# alpha_board.net
KiCad netlist of a schematic drawn in EAGLE
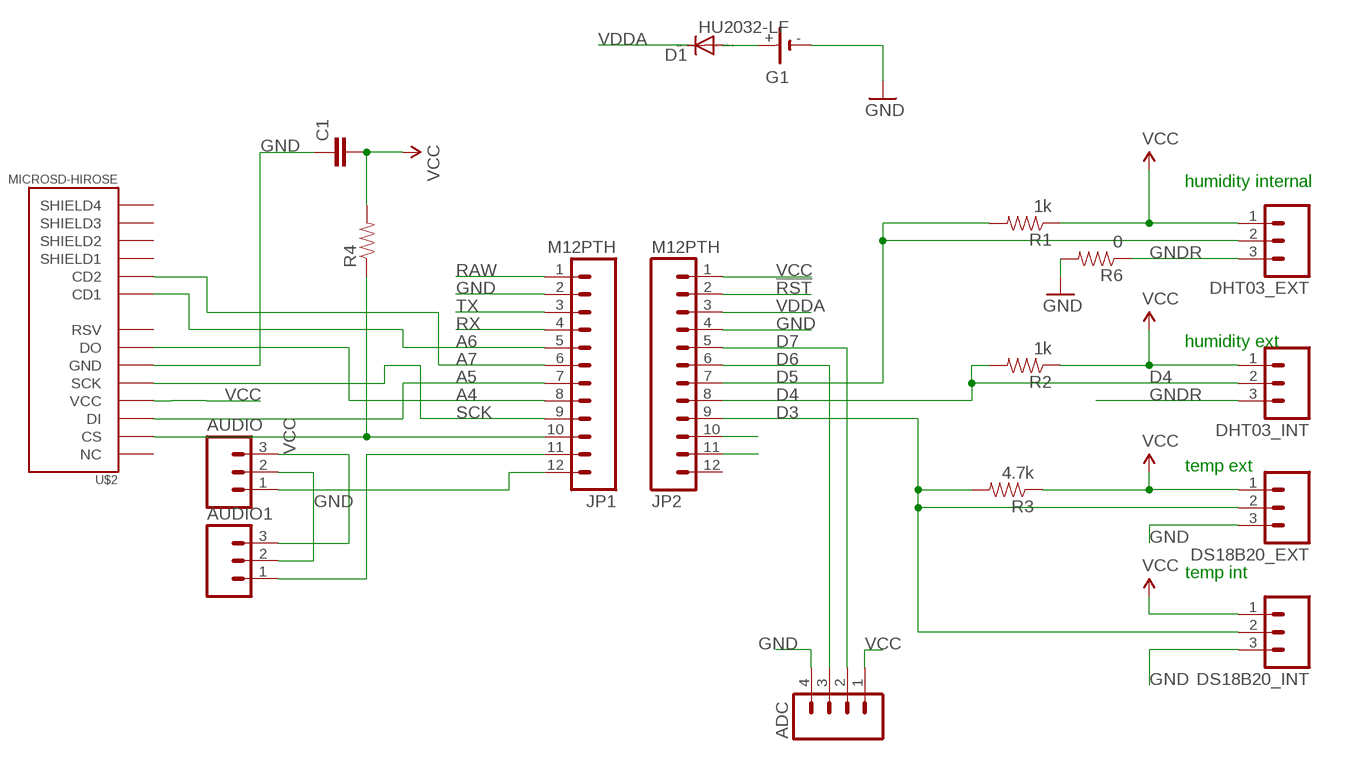
[diagram p0: schematic, sheet 1]

(export (version "E")
  (design (tool "Eeschema 10.0.6"))
  (components
    (comp (ref "ADC")
      (value "M04LOCK_LONGPADS")
      (footprint "eagle-import:1X04_LOCK_LONGPADS")
      (libsource (lib "eagle-import") (part "M04LOCK_LONGPADS"))
    )
    (comp (ref "AUDIO")
      (value "M03LOCK")
      (footprint "eagle-import:1X03_LOCK")
      (libsource (lib "eagle-import") (part "M03LOCK"))
    )
    (comp (ref "AUDIO1")
      (value "M03LOCK")
      (footprint "eagle-import:1X03_LOCK")
      (libsource (lib "eagle-import") (part "M03LOCK"))
    )
    (comp (ref "C1")
      (value "CAP1206")
      (footprint "eagle-import:1206")
      (libsource (lib "eagle-import") (part "CAP1206"))
    )
    (comp (ref "D1")
      (value "DIODE-SOD323-W")
      (footprint "eagle-import:SOD323-W")
      (libsource (lib "eagle-import") (part "DIODE-SOD323-W"))
    )
    (comp (ref "DHT03_EXT")
      (value "M03LOCK")
      (footprint "eagle-import:1X03_LOCK")
      (libsource (lib "eagle-import") (part "M03LOCK"))
    )
    (comp (ref "DHT03_INT")
      (value "M03LOCK")
      (footprint "eagle-import:1X03_LOCK")
      (libsource (lib "eagle-import") (part "M03LOCK"))
    )
    (comp (ref "DS18B20_EXT")
      (value "M03LOCK")
      (footprint "eagle-import:1X03_LOCK")
      (libsource (lib "eagle-import") (part "M03LOCK"))
    )
    (comp (ref "DS18B20_INT")
      (value "M03LOCK")
      (footprint "eagle-import:1X03_LOCK")
      (libsource (lib "eagle-import") (part "M03LOCK"))
    )
    (comp (ref "G1")
      (value "HU2032-LF")
      (footprint "eagle-import:HU2032-LF")
      (libsource (lib "eagle-import") (part "HU2032-LF"))
    )
    (comp (ref "JP1")
      (value "M12PTH")
      (footprint "eagle-import:1X12-SMALL-PADS")
      (libsource (lib "eagle-import") (part "M12PTH"))
    )
    (comp (ref "JP2")
      (value "M12PTH")
      (footprint "eagle-import:1X12-SMALL-PADS")
      (libsource (lib "eagle-import") (part "M12PTH"))
    )
    (comp (ref "R1")
      (value "1k")
      (footprint "eagle-import:1206")
      (libsource (lib "eagle-import") (part "RESISTOR1206"))
    )
    (comp (ref "R2")
      (value "1k")
      (footprint "eagle-import:1206")
      (libsource (lib "eagle-import") (part "RESISTOR1206"))
    )
    (comp (ref "R3")
      (value "4.7k")
      (footprint "eagle-import:1206")
      (libsource (lib "eagle-import") (part "RESISTOR1206"))
    )
    (comp (ref "R4")
      (value "RESISTOR1206")
      (footprint "eagle-import:1206")
      (libsource (lib "eagle-import") (part "RESISTOR1206"))
    )
    (comp (ref "R6")
      (value "0")
      (footprint "eagle-import:1206")
      (libsource (lib "eagle-import") (part "RESISTOR1206"))
    )
    (comp (ref "U$2")
      (value "MICROSD-HIROSE")
      (footprint "eagle-import:MICROSD_HOLDER-HIROSE-DM3AT")
      (libsource (lib "eagle-import") (part "MICROSD-HIROSE"))
    )
  )
  (nets
    (net (code "1") (name "/A4") (class "Default")
      (node (ref "JP1") (pin "8") (pinfunction "8_8") (pintype "passive"))
      (node (ref "U$2") (pin "DAT0") (pinfunction "DO_DAT0") (pintype "bidirectional"))
    )
    (net (code "2") (name "/A5") (class "Default")
      (node (ref "JP1") (pin "7") (pinfunction "7_7") (pintype "passive"))
      (node (ref "U$2") (pin "CMD") (pinfunction "DI_CMD") (pintype "bidirectional"))
    )
    (net (code "3") (name "/A6") (class "Default")
      (node (ref "JP1") (pin "5") (pinfunction "5_5") (pintype "passive"))
      (node (ref "U$2") (pin "CD1") (pinfunction "CD1_CD1") (pintype "bidirectional"))
    )
    (net (code "4") (name "/A7") (class "Default")
      (node (ref "JP1") (pin "6") (pinfunction "6_6") (pintype "passive"))
      (node (ref "U$2") (pin "CD2") (pinfunction "CD2_CD2") (pintype "bidirectional"))
    )
    (net (code "5") (name "/D3") (class "Default")
      (node (ref "DS18B20_EXT") (pin "2") (pinfunction "2_2") (pintype "passive"))
      (node (ref "DS18B20_INT") (pin "2") (pinfunction "2_2") (pintype "passive"))
      (node (ref "JP2") (pin "9") (pinfunction "9_9") (pintype "passive"))
      (node (ref "R3") (pin "2") (pinfunction "2_2") (pintype "passive"))
    )
    (net (code "6") (name "/D4") (class "Default")
      (node (ref "DHT03_INT") (pin "2") (pinfunction "2_2") (pintype "passive"))
      (node (ref "JP2") (pin "8") (pinfunction "8_8") (pintype "passive"))
      (node (ref "R2") (pin "2") (pinfunction "2_2") (pintype "passive"))
    )
    (net (code "7") (name "/D5") (class "Default")
      (node (ref "DHT03_EXT") (pin "2") (pinfunction "2_2") (pintype "passive"))
      (node (ref "JP2") (pin "7") (pinfunction "7_7") (pintype "passive"))
      (node (ref "R1") (pin "2") (pinfunction "2_2") (pintype "passive"))
    )
    (net (code "8") (name "/D6") (class "Default")
      (node (ref "ADC") (pin "3") (pinfunction "3_3") (pintype "passive"))
      (node (ref "JP2") (pin "6") (pinfunction "6_6") (pintype "passive"))
    )
    (net (code "9") (name "/D7") (class "Default")
      (node (ref "ADC") (pin "2") (pinfunction "2_2") (pintype "passive"))
      (node (ref "JP2") (pin "5") (pinfunction "5_5") (pintype "passive"))
    )
    (net (code "10") (name "/GNDR") (class "Default")
      (node (ref "DHT03_EXT") (pin "3") (pinfunction "3_3") (pintype "passive"))
      (node (ref "DHT03_INT") (pin "3") (pinfunction "3_3") (pintype "passive"))
      (node (ref "R6") (pin "1") (pinfunction "1_1") (pintype "passive"))
    )
    (net (code "11") (name "/RAW") (class "Default")
      (node (ref "JP1") (pin "1") (pinfunction "1_1") (pintype "passive"))
    )
    (net (code "12") (name "/RX") (class "Default")
      (node (ref "JP1") (pin "4") (pinfunction "4_4") (pintype "passive"))
    )
    (net (code "13") (name "/SCK") (class "Default")
      (node (ref "JP1") (pin "9") (pinfunction "9_9") (pintype "passive"))
      (node (ref "U$2") (pin "CLK") (pinfunction "SCK_CLK") (pintype "bidirectional"))
    )
    (net (code "14") (name "/TX") (class "Default")
      (node (ref "JP1") (pin "3") (pinfunction "3_3") (pintype "passive"))
    )
    (net (code "15") (name "/VDDA") (class "Default")
      (node (ref "D1") (pin "C") (pinfunction "C_C") (pintype "passive"))
      (node (ref "JP2") (pin "3") (pinfunction "3_3") (pintype "passive"))
    )
    (net (code "16") (name "/~{RST}") (class "Default")
      (node (ref "JP2") (pin "2") (pinfunction "2_2") (pintype "passive"))
    )
    (net (code "17") (name "GND") (class "Default")
      (node (ref "ADC") (pin "4") (pinfunction "4_4") (pintype "passive"))
      (node (ref "AUDIO") (pin "2") (pinfunction "2_2") (pintype "passive"))
      (node (ref "AUDIO1") (pin "2") (pinfunction "2_2") (pintype "passive"))
      (node (ref "C1") (pin "1") (pinfunction "1_1") (pintype "passive"))
      (node (ref "DS18B20_EXT") (pin "3") (pinfunction "3_3") (pintype "passive"))
      (node (ref "DS18B20_INT") (pin "3") (pinfunction "3_3") (pintype "passive"))
      (node (ref "G1") (pin "-") (pinfunction "-_-") (pintype "passive"))
      (node (ref "JP1") (pin "2") (pinfunction "2_2") (pintype "passive"))
      (node (ref "JP2") (pin "4") (pinfunction "4_4") (pintype "passive"))
      (node (ref "R6") (pin "2") (pinfunction "2_2") (pintype "passive"))
      (node (ref "U$2") (pin "VSS") (pinfunction "GND_VSS") (pintype "power_in"))
    )
    (net (code "18") (name "Net-(AUDIO-Pad1)") (class "Default")
      (node (ref "AUDIO") (pin "1") (pinfunction "1_1") (pintype "passive"))
      (node (ref "JP1") (pin "12") (pinfunction "12_12") (pintype "passive"))
    )
    (net (code "19") (name "Net-(AUDIO1-Pad1)") (class "Default")
      (node (ref "AUDIO1") (pin "1") (pinfunction "1_1") (pintype "passive"))
      (node (ref "JP1") (pin "11") (pinfunction "11_11") (pintype "passive"))
    )
    (net (code "20") (name "Net-(D1-PadA)") (class "Default")
      (node (ref "D1") (pin "A") (pinfunction "A_A") (pintype "passive"))
      (node (ref "G1") (pin "+") (pinfunction "+_+") (pintype "passive"))
    )
    (net (code "21") (name "Net-(U$2-CS)") (class "Default")
      (node (ref "JP1") (pin "10") (pinfunction "10_10") (pintype "passive"))
      (node (ref "R4") (pin "1") (pinfunction "1_1") (pintype "passive"))
      (node (ref "U$2") (pin "DAT3") (pinfunction "CS_DAT3") (pintype "bidirectional"))
    )
    (net (code "22") (name "VCC") (class "Default")
      (node (ref "ADC") (pin "1") (pinfunction "1_1") (pintype "passive"))
      (node (ref "AUDIO") (pin "3") (pinfunction "3_3") (pintype "passive"))
      (node (ref "AUDIO1") (pin "3") (pinfunction "3_3") (pintype "passive"))
      (node (ref "C1") (pin "2") (pinfunction "2_2") (pintype "passive"))
      (node (ref "DHT03_EXT") (pin "1") (pinfunction "1_1") (pintype "passive"))
      (node (ref "DHT03_INT") (pin "1") (pinfunction "1_1") (pintype "passive"))
      (node (ref "DS18B20_EXT") (pin "1") (pinfunction "1_1") (pintype "passive"))
      (node (ref "DS18B20_INT") (pin "1") (pinfunction "1_1") (pintype "passive"))
      (node (ref "JP2") (pin "1") (pinfunction "1_1") (pintype "passive"))
      (node (ref "R1") (pin "1") (pinfunction "1_1") (pintype "passive"))
      (node (ref "R2") (pin "1") (pinfunction "1_1") (pintype "passive"))
      (node (ref "R3") (pin "1") (pinfunction "1_1") (pintype "passive"))
      (node (ref "R4") (pin "2") (pinfunction "2_2") (pintype "passive"))
      (node (ref "U$2") (pin "VDD") (pinfunction "VCC_VDD") (pintype "power_in"))
    )
    (net (code "23") (name "unconnected-(G1-+-Pad+@1)") (class "Default")
      (node (ref "G1") (pin "+@1") (pinfunction "+_+@1") (pintype "passive"))
    )
    (net (code "24") (name "unconnected-(JP2-Pad10)") (class "Default")
      (node (ref "JP2") (pin "10") (pinfunction "10_10") (pintype "passive"))
    )
    (net (code "25") (name "unconnected-(JP2-Pad11)") (class "Default")
      (node (ref "JP2") (pin "11") (pinfunction "11_11") (pintype "passive"))
    )
    (net (code "26") (name "unconnected-(JP2-Pad12)") (class "Default")
      (node (ref "JP2") (pin "12") (pinfunction "12_12") (pintype "passive"))
    )
    (net (code "27") (name "unconnected-(U$2-NC-PadDAT2)") (class "Default")
      (node (ref "U$2") (pin "DAT2") (pinfunction "NC_DAT2") (pintype "bidirectional"))
    )
    (net (code "28") (name "unconnected-(U$2-RSV-PadDAT1)") (class "Default")
      (node (ref "U$2") (pin "DAT1") (pinfunction "RSV_DAT1") (pintype "bidirectional"))
    )
    (net (code "29") (name "unconnected-(U$2-SHIELD1-PadBODY1)") (class "Default")
      (node (ref "U$2") (pin "BODY1") (pinfunction "SHIELD1_BODY1") (pintype "bidirectional"))
    )
    (net (code "30") (name "unconnected-(U$2-SHIELD2-PadBODY2)") (class "Default")
      (node (ref "U$2") (pin "BODY2") (pinfunction "SHIELD2_BODY2") (pintype "bidirectional"))
    )
    (net (code "31") (name "unconnected-(U$2-SHIELD3-PadBODY3)") (class "Default")
      (node (ref "U$2") (pin "BODY3") (pinfunction "SHIELD3_BODY3") (pintype "bidirectional"))
    )
    (net (code "32") (name "unconnected-(U$2-SHIELD4-PadBODY4)") (class "Default")
      (node (ref "U$2") (pin "BODY4") (pinfunction "SHIELD4_BODY4") (pintype "bidirectional"))
    )
  )
)
